# SPI_1.net
KiCad netlist of a schematic drawn in Altium Designer
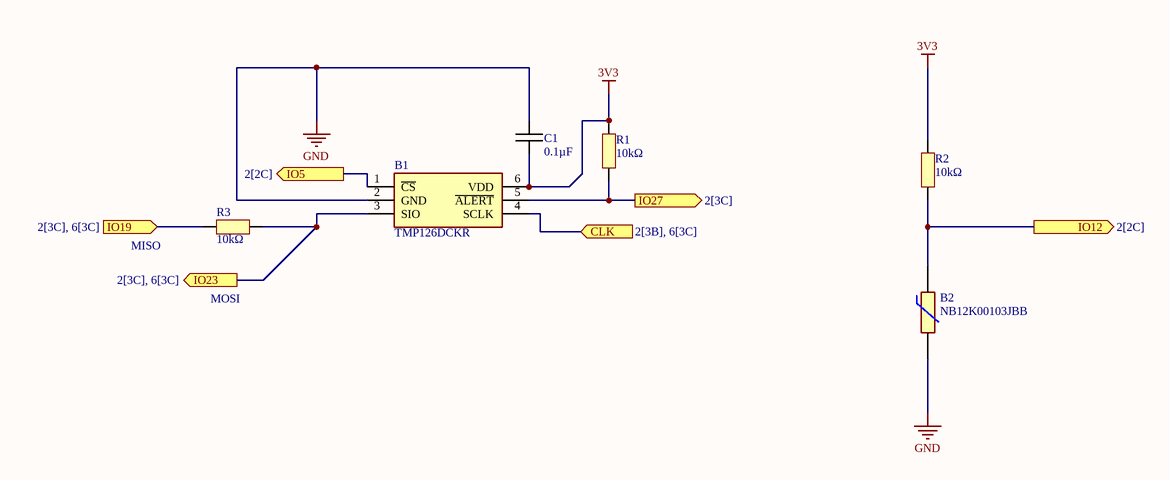
[diagram p0: SPI 1.SchDoc]

(export (version "E")
  (design (tool "Eeschema 10.0.6"))
  (components
    (comp (ref "B1")
      (value "TMP126DCKR")
      (footprint "SOT65P210X110-6N")
      (fields (field (name "MOUSER PART NUMBER") "595-TMP126DCKR"))
      (libsource (lib "SCHLibrary") (part "TMP126DCKR"))
    )
    (comp (ref "B2")
      (value "NB12K00103JBB")
      (footprint "RESC2212X50N")
      (description "NTC SMD Thermistor, NB12K, 10K, 5% AVX 10k 0805 Protection NTC Thermistor, 5s, 2 x 1.25 x 1.3mm")
      (fields (field (name "MOUSER PART NUMBER") "581-NB12K00103JBB"))
      (libsource (lib "SCHLibrary") (part "NB12K00103JBB"))
    )
    (comp (ref "C1")
      (value "0.1µF")
      (footprint "CAPC1005X06N")
      (libsource (lib "SCHLibrary") (part "Capacitor"))
    )
    (comp (ref "R1")
      (value "10kΩ")
      (footprint "RESC1005X06N")
      (libsource (lib "SCHLibrary") (part "Resistor"))
    )
    (comp (ref "R2") (value "10kΩ") (footprint "RESC1005X06N") (libsource (lib "") (part "Resistor_2")))
    (comp (ref "R3") (value "10kΩ") (footprint "RESC1005X06N") (libsource (lib "") (part "Resistor_1")))
  )
  (nets
    (net (code "1") (name "/CLK") (class "Default")
      (node (ref "B1") (pin "4") (pinfunction "SCLK_4") (pintype "passive"))
    )
    (net (code "2") (name "/IO5") (class "Default")
      (node (ref "B1") (pin "1") (pinfunction "~{CS}_1") (pintype "passive"))
    )
    (net (code "3") (name "/IO12") (class "Default")
      (node (ref "B2") (pin "1") (pinfunction "1_1") (pintype "passive"))
      (node (ref "R2") (pin "2") (pinfunction "2_2") (pintype "passive"))
    )
    (net (code "4") (name "/IO19") (class "Default")
      (node (ref "R3") (pin "2") (pinfunction "2_2") (pintype "passive"))
    )
    (net (code "5") (name "/IO23") (class "Default")
      (node (ref "B1") (pin "3") (pinfunction "SIO_3") (pintype "passive"))
      (node (ref "R3") (pin "1") (pinfunction "1_1") (pintype "passive"))
    )
    (net (code "6") (name "/IO27") (class "Default")
      (node (ref "B1") (pin "5") (pinfunction "~{ALERT}_5") (pintype "passive"))
      (node (ref "R1") (pin "1") (pinfunction "1_1") (pintype "passive"))
    )
    (net (code "7") (name "3V3") (class "Default")
      (node (ref "B1") (pin "6") (pinfunction "VDD_6") (pintype "passive"))
      (node (ref "C1") (pin "1") (pinfunction "1_1") (pintype "passive"))
      (node (ref "R1") (pin "2") (pinfunction "2_2") (pintype "passive"))
      (node (ref "R2") (pin "1") (pinfunction "1_1") (pintype "passive"))
    )
    (net (code "8") (name "GND") (class "Default")
      (node (ref "B1") (pin "2") (pinfunction "GND_2") (pintype "passive"))
      (node (ref "B2") (pin "2") (pinfunction "2_2") (pintype "passive"))
      (node (ref "C1") (pin "2") (pinfunction "2_2") (pintype "passive"))
    )
  )
)
